# Delay_circuit_555.net
KiCad netlist of a schematic drawn in EAGLE
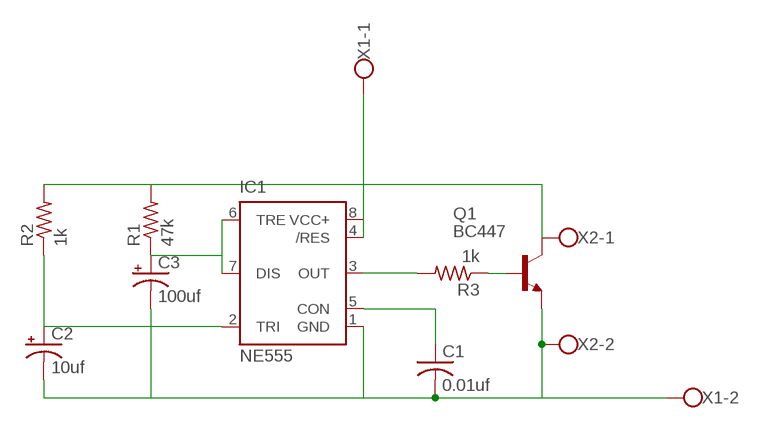
[diagram p0: schematic, sheet 1]

(export (version "E")
  (design (tool "Eeschema 10.0.6"))
  (components
    (comp (ref "C1")
      (value "0.01uf")
      (footprint "eagle-import:C025-025X050")
      (libsource (lib "eagle-import") (part "C-US025-025X050"))
    )
    (comp (ref "C2")
      (value "10uf")
      (footprint "eagle-import:E2,5-6")
      (libsource (lib "eagle-import") (part "CPOL-USE2.5-6"))
    )
    (comp (ref "C3")
      (value "100uf")
      (footprint "eagle-import:E2,5-6")
      (libsource (lib "eagle-import") (part "CPOL-USE2.5-6"))
    )
    (comp (ref "IC1")
      (value "NE555")
      (footprint "eagle-import:DIL-08")
      (fields (field (name "MF") "Arrow Electronics") (field (name "MPN") "NE555N"))
      (libsource (lib "eagle-import") (part "NE555"))
    )
    (comp (ref "Q1")
      (value "BC447")
      (footprint "eagle-import:TO92-EBC")
      (libsource (lib "eagle-import") (part "BC447"))
    )
    (comp (ref "R1")
      (value "47k")
      (footprint "eagle-import:0207_10")
      (libsource (lib "eagle-import") (part "R-US_0207/10"))
    )
    (comp (ref "R2")
      (value "1k")
      (footprint "eagle-import:0207_10")
      (libsource (lib "eagle-import") (part "R-US_0207/10"))
    )
    (comp (ref "R3")
      (value "1k")
      (footprint "eagle-import:0207_10")
      (libsource (lib "eagle-import") (part "R-US_0207/10"))
    )
    (comp (ref "X1")
      (value "W237-102")
      (footprint "eagle-import:W237-102")
      (fields (field (name "MPN") "237-102"))
      (libsource (lib "eagle-import") (part "W237-102"))
    )
    (comp (ref "X2")
      (value "W237-102")
      (footprint "eagle-import:W237-102")
      (fields (field (name "MPN") "237-102"))
      (libsource (lib "eagle-import") (part "W237-102"))
    )
  )
  (nets
    (net (code "1") (name "Net-(IC1-CON)") (class "Default")
      (node (ref "C1") (pin "1") (pinfunction "1_1") (pintype "passive"))
      (node (ref "IC1") (pin "5") (pinfunction "CON_5") (pintype "input"))
    )
    (net (code "2") (name "Net-(IC1-DIS)") (class "Default")
      (node (ref "C3") (pin "+") (pinfunction "+_+") (pintype "passive"))
      (node (ref "IC1") (pin "6") (pinfunction "TRE_6") (pintype "input"))
      (node (ref "IC1") (pin "7") (pinfunction "DIS_7") (pintype "input"))
      (node (ref "R1") (pin "1") (pinfunction "1_1") (pintype "passive"))
    )
    (net (code "3") (name "Net-(IC1-GND)") (class "Default")
      (node (ref "C1") (pin "2") (pinfunction "2_2") (pintype "passive"))
      (node (ref "C2") (pin "-") (pinfunction "-_-") (pintype "passive"))
      (node (ref "C3") (pin "-") (pinfunction "-_-") (pintype "passive"))
      (node (ref "IC1") (pin "1") (pinfunction "GND_1") (pintype "power_in"))
      (node (ref "Q1") (pin "E") (pinfunction "E_E") (pintype "passive"))
      (node (ref "X1") (pin "2") (pinfunction "KL_2") (pintype "passive"))
      (node (ref "X2") (pin "2") (pinfunction "KL_2") (pintype "passive"))
    )
    (net (code "4") (name "Net-(IC1-OUT)") (class "Default")
      (node (ref "IC1") (pin "3") (pinfunction "OUT_3") (pintype "output"))
      (node (ref "R3") (pin "2") (pinfunction "2_2") (pintype "passive"))
    )
    (net (code "5") (name "Net-(IC1-TRI)") (class "Default")
      (node (ref "C2") (pin "+") (pinfunction "+_+") (pintype "passive"))
      (node (ref "IC1") (pin "2") (pinfunction "TRI_2") (pintype "input"))
      (node (ref "R2") (pin "1") (pinfunction "1_1") (pintype "passive"))
    )
    (net (code "6") (name "Net-(IC1-VCC+)") (class "Default")
      (node (ref "IC1") (pin "4") (pinfunction "/RES_4") (pintype "input"))
      (node (ref "IC1") (pin "8") (pinfunction "VCC+_8") (pintype "power_in"))
      (node (ref "Q1") (pin "C") (pinfunction "C_C") (pintype "passive"))
      (node (ref "R1") (pin "2") (pinfunction "2_2") (pintype "passive"))
      (node (ref "R2") (pin "2") (pinfunction "2_2") (pintype "passive"))
      (node (ref "X1") (pin "1") (pinfunction "KL_1") (pintype "passive"))
      (node (ref "X2") (pin "1") (pinfunction "KL_1") (pintype "passive"))
    )
    (net (code "7") (name "Net-(Q1-PadB)") (class "Default")
      (node (ref "Q1") (pin "B") (pinfunction "B_B") (pintype "passive"))
      (node (ref "R3") (pin "1") (pinfunction "1_1") (pintype "passive"))
    )
  )
)
